# SoftStart_V1_0_TO_PRINT.net
KiCad netlist of a schematic drawn in EAGLE
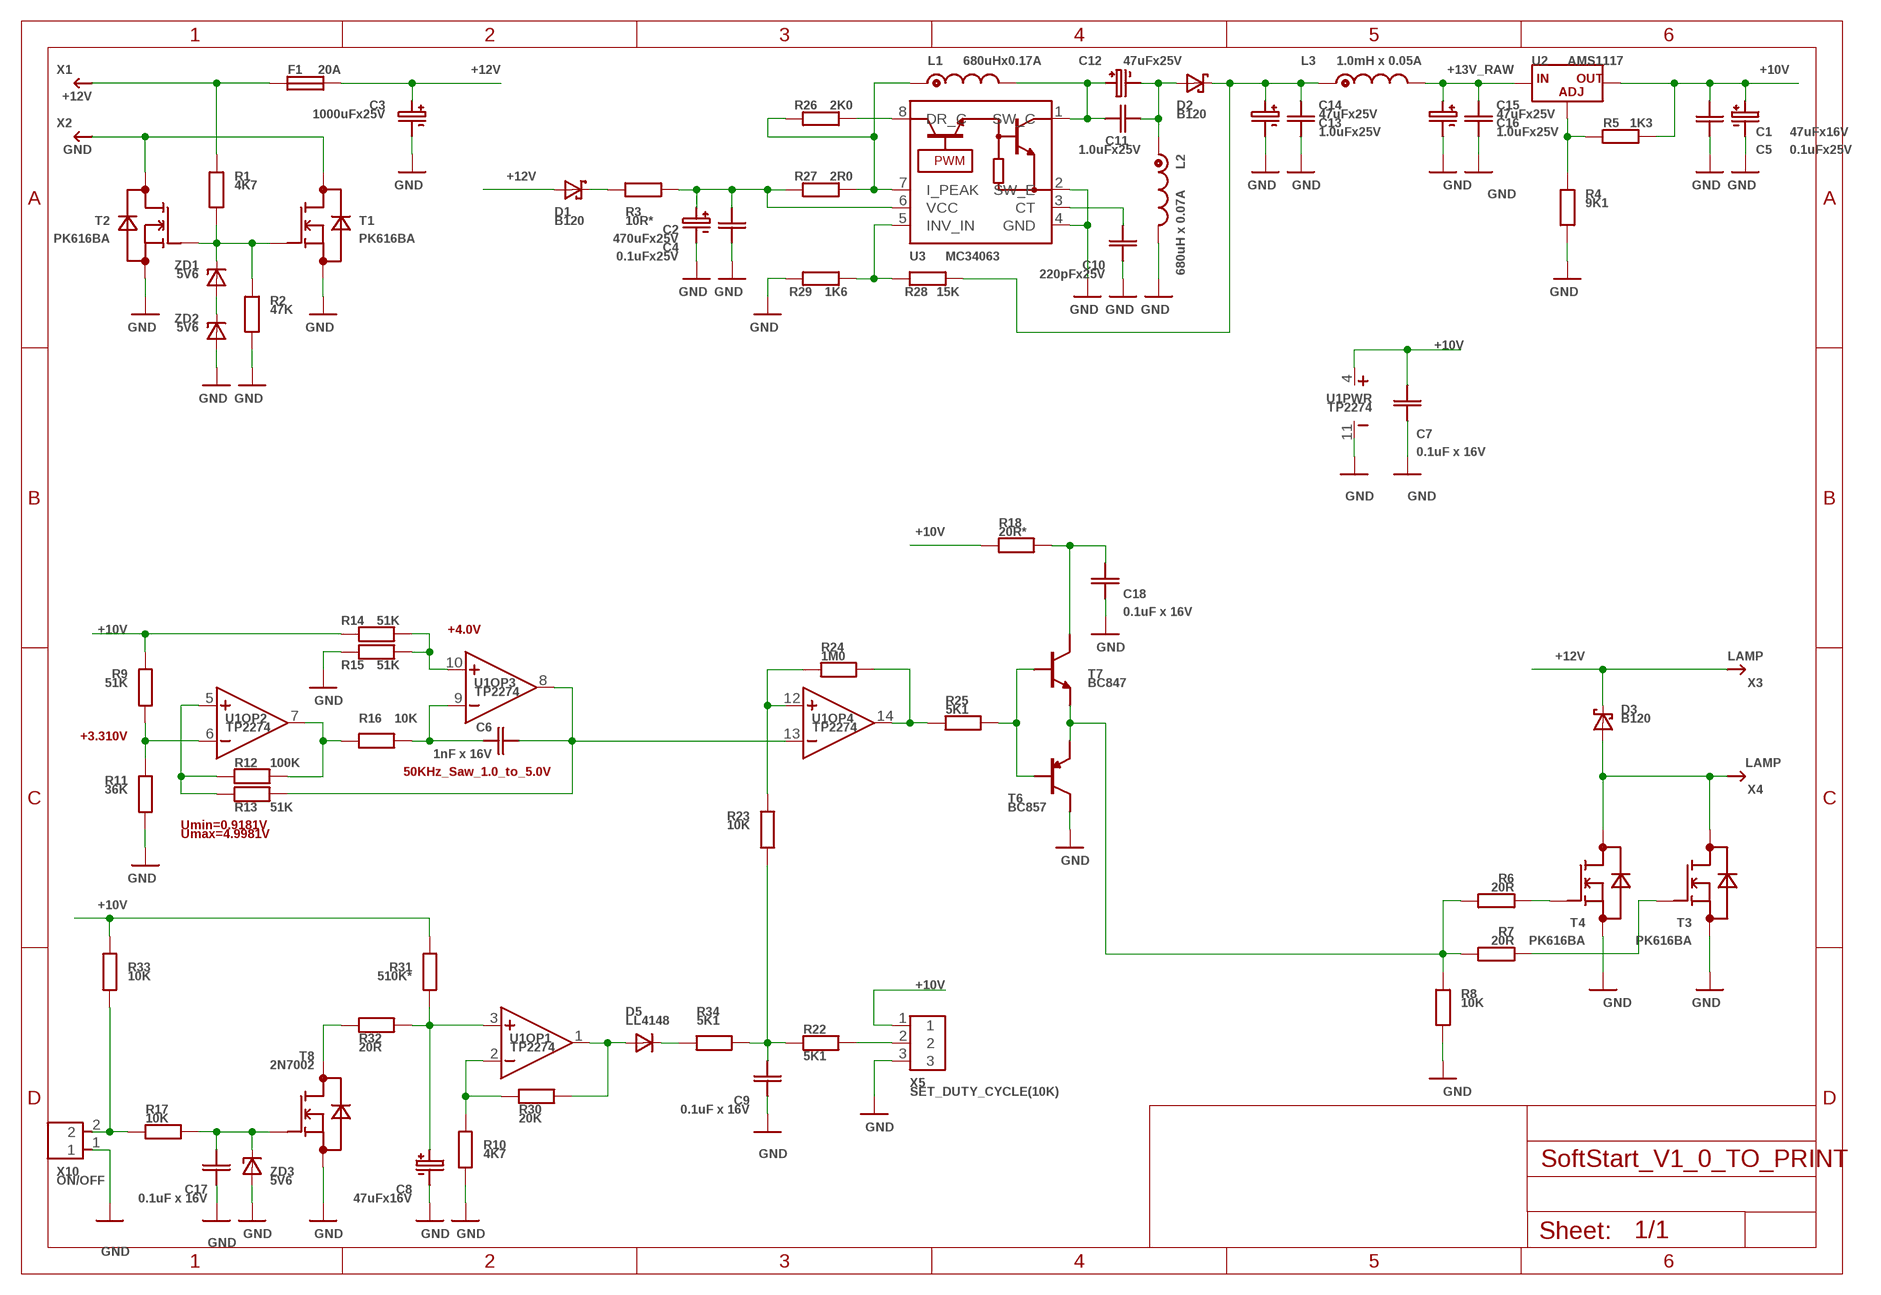
[diagram p0: schematic, sheet 1]

(export (version "E")
  (design (tool "Eeschema 10.0.6"))
  (components
    (comp (ref "C1")
      (value "47uFx16V")
      (footprint "eagle-import:CE_6.3MM")
      (libsource (lib "eagle-import") (part "CE6.3MM"))
    )
    (comp (ref "C2")
      (value "470uFx25V")
      (footprint "eagle-import:CE_10MM")
      (libsource (lib "eagle-import") (part "CE10MM"))
    )
    (comp (ref "C3")
      (value "1000uFx25V")
      (footprint "eagle-import:CE_10MM")
      (libsource (lib "eagle-import") (part "CE10MM"))
    )
    (comp (ref "C4")
      (value "0.1uFx25V")
      (footprint "eagle-import:RSMD_1206")
      (libsource (lib "eagle-import") (part "CSMD_1206"))
    )
    (comp (ref "C5")
      (value "0.1uFx25V")
      (footprint "eagle-import:RSMD_0805")
      (libsource (lib "eagle-import") (part "CSMD_0805"))
    )
    (comp (ref "C6")
      (value "1nF x 16V")
      (footprint "eagle-import:RSMD_0805")
      (libsource (lib "eagle-import") (part "CSMD_0805"))
    )
    (comp (ref "C7")
      (value "0.1uF x 16V")
      (footprint "eagle-import:RSMD_0805")
      (libsource (lib "eagle-import") (part "CSMD_0805"))
    )
    (comp (ref "C8")
      (value "47uFx16V")
      (footprint "eagle-import:CE_6.3MM")
      (libsource (lib "eagle-import") (part "CE6.3MM"))
    )
    (comp (ref "C9")
      (value "0.1uF x 16V")
      (footprint "eagle-import:RSMD_0805")
      (libsource (lib "eagle-import") (part "CSMD_0805"))
    )
    (comp (ref "C10")
      (value "220pFx25V")
      (footprint "eagle-import:RSMD_0805")
      (libsource (lib "eagle-import") (part "CSMD_0805"))
    )
    (comp (ref "C11")
      (value "1.0uFx25V")
      (footprint "eagle-import:RSMD_1206")
      (libsource (lib "eagle-import") (part "CSMD_1206"))
    )
    (comp (ref "C12")
      (value "47uFx25V")
      (footprint "eagle-import:CE_6.3MM")
      (libsource (lib "eagle-import") (part "CE6.3MM"))
    )
    (comp (ref "C13")
      (value "1.0uFx25V")
      (footprint "eagle-import:RSMD_1206")
      (libsource (lib "eagle-import") (part "CSMD_1206"))
    )
    (comp (ref "C14")
      (value "47uFx25V")
      (footprint "eagle-import:CE_6.3MM")
      (libsource (lib "eagle-import") (part "CE6.3MM"))
    )
    (comp (ref "C15")
      (value "47uFx25V")
      (footprint "eagle-import:CE_6.3MM")
      (libsource (lib "eagle-import") (part "CE6.3MM"))
    )
    (comp (ref "C16")
      (value "1.0uFx25V")
      (footprint "eagle-import:RSMD_1206")
      (libsource (lib "eagle-import") (part "CSMD_1206"))
    )
    (comp (ref "C17")
      (value "0.1uF x 16V")
      (footprint "eagle-import:RSMD_0805")
      (libsource (lib "eagle-import") (part "CSMD_0805"))
    )
    (comp (ref "C18")
      (value "0.1uF x 16V")
      (footprint "eagle-import:RSMD_0805")
      (libsource (lib "eagle-import") (part "CSMD_0805"))
    )
    (comp (ref "D1")
      (value "B120")
      (footprint "eagle-import:DO-214AC")
      (libsource (lib "eagle-import") (part "B120(DO-214AC)"))
    )
    (comp (ref "D2")
      (value "B120")
      (footprint "eagle-import:DO-214AC")
      (libsource (lib "eagle-import") (part "B120(DO-214AC)"))
    )
    (comp (ref "D3")
      (value "B120")
      (footprint "eagle-import:DO-214AC")
      (libsource (lib "eagle-import") (part "B120(DO-214AC)"))
    )
    (comp (ref "D5")
      (value "LL4148")
      (footprint "eagle-import:SOD-80")
      (libsource (lib "eagle-import") (part "LL4147SOD-80"))
    )
    (comp (ref "F1")
      (value "20A")
      (footprint "eagle-import:FUSE_AUTO_MINI_ON_TERMINALS")
      (libsource (lib "eagle-import") (part "FUSEAUTO_MINI_TERMINALS"))
    )
    (comp (ref "L1")
      (value "680uHx0.17A")
      (footprint "eagle-import:LCHB0608")
      (libsource (lib "eagle-import") (part "L(LCHB0608)"))
    )
    (comp (ref "L2")
      (value "680uH x 0.07A")
      (footprint "eagle-import:LCHB0608")
      (libsource (lib "eagle-import") (part "L(LCHB0608)"))
    )
    (comp (ref "L3")
      (value "1.0mH x 0.05A")
      (footprint "eagle-import:LCHB0608")
      (libsource (lib "eagle-import") (part "L(LCHB0608)"))
    )
    (comp (ref "R1")
      (value "4K7")
      (footprint "eagle-import:RSMD_0805")
      (libsource (lib "eagle-import") (part "RSMD_0805"))
    )
    (comp (ref "R2")
      (value "47K")
      (footprint "eagle-import:RSMD_0805")
      (libsource (lib "eagle-import") (part "RSMD_0805"))
    )
    (comp (ref "R3")
      (value "10R*")
      (footprint "eagle-import:RSMD_1206_BIG_GAP")
      (libsource (lib "eagle-import") (part "RSMD_1206_BIG_GAP"))
    )
    (comp (ref "R4")
      (value "9K1")
      (footprint "eagle-import:RSMD_0805")
      (libsource (lib "eagle-import") (part "RSMD_0805"))
    )
    (comp (ref "R5")
      (value "1K3")
      (footprint "eagle-import:RSMD_0805")
      (libsource (lib "eagle-import") (part "RSMD_0805"))
    )
    (comp (ref "R6")
      (value "20R")
      (footprint "eagle-import:RSMD_0805")
      (libsource (lib "eagle-import") (part "RSMD_0805"))
    )
    (comp (ref "R7")
      (value "20R")
      (footprint "eagle-import:RSMD_0805")
      (libsource (lib "eagle-import") (part "RSMD_0805"))
    )
    (comp (ref "R8")
      (value "10K")
      (footprint "eagle-import:RSMD_0805")
      (libsource (lib "eagle-import") (part "RSMD_0805"))
    )
    (comp (ref "R9")
      (value "51K")
      (footprint "eagle-import:RSMD_0805")
      (libsource (lib "eagle-import") (part "RSMD_0805"))
    )
    (comp (ref "R10")
      (value "4K7")
      (footprint "eagle-import:RSMD_0805")
      (libsource (lib "eagle-import") (part "RSMD_0805"))
    )
    (comp (ref "R11")
      (value "36K")
      (footprint "eagle-import:RSMD_0805")
      (libsource (lib "eagle-import") (part "RSMD_0805"))
    )
    (comp (ref "R12")
      (value "100K")
      (footprint "eagle-import:RSMD_0805")
      (libsource (lib "eagle-import") (part "RSMD_0805"))
    )
    (comp (ref "R13")
      (value "51K")
      (footprint "eagle-import:RSMD_0805")
      (libsource (lib "eagle-import") (part "RSMD_0805"))
    )
    (comp (ref "R14")
      (value "51K")
      (footprint "eagle-import:RSMD_0805")
      (libsource (lib "eagle-import") (part "RSMD_0805"))
    )
    (comp (ref "R15")
      (value "51K")
      (footprint "eagle-import:RSMD_0805")
      (libsource (lib "eagle-import") (part "RSMD_0805"))
    )
    (comp (ref "R16")
      (value "10K")
      (footprint "eagle-import:RSMD_0805")
      (libsource (lib "eagle-import") (part "RSMD_0805"))
    )
    (comp (ref "R17")
      (value "10K")
      (footprint "eagle-import:RSMD_0805")
      (libsource (lib "eagle-import") (part "RSMD_0805"))
    )
    (comp (ref "R18")
      (value "20R*")
      (footprint "eagle-import:RSMD_1206")
      (libsource (lib "eagle-import") (part "RSMD_1206"))
    )
    (comp (ref "R22")
      (value "5K1")
      (footprint "eagle-import:RSMD_0805")
      (libsource (lib "eagle-import") (part "RSMD_0805"))
    )
    (comp (ref "R23")
      (value "10K")
      (footprint "eagle-import:RSMD_1206_BIG_GAP")
      (libsource (lib "eagle-import") (part "RSMD_1206_BIG_GAP"))
    )
    (comp (ref "R24")
      (value "1M0")
      (footprint "eagle-import:RSMD_0805")
      (libsource (lib "eagle-import") (part "RSMD_0805"))
    )
    (comp (ref "R25")
      (value "5K1")
      (footprint "eagle-import:RSMD_0805")
      (libsource (lib "eagle-import") (part "RSMD_0805"))
    )
    (comp (ref "R26")
      (value "2K0")
      (footprint "eagle-import:RSMD_0805")
      (libsource (lib "eagle-import") (part "RSMD_0805"))
    )
    (comp (ref "R27")
      (value "2R0")
      (footprint "eagle-import:RSMD_1206_BIG_GAP")
      (libsource (lib "eagle-import") (part "RSMD_1206_BIG_GAP"))
    )
    (comp (ref "R28")
      (value "15K")
      (footprint "eagle-import:RSMD_0805")
      (libsource (lib "eagle-import") (part "RSMD_0805"))
    )
    (comp (ref "R29")
      (value "1K6")
      (footprint "eagle-import:RSMD_0805")
      (libsource (lib "eagle-import") (part "RSMD_0805"))
    )
    (comp (ref "R30")
      (value "20K")
      (footprint "eagle-import:RSMD_0805")
      (libsource (lib "eagle-import") (part "RSMD_0805"))
    )
    (comp (ref "R31")
      (value "510K*")
      (footprint "eagle-import:RSMD_0805")
      (libsource (lib "eagle-import") (part "RSMD_0805"))
    )
    (comp (ref "R32")
      (value "20R")
      (footprint "eagle-import:RSMD_0805")
      (libsource (lib "eagle-import") (part "RSMD_0805"))
    )
    (comp (ref "R33")
      (value "10K")
      (footprint "eagle-import:RSMD_0805")
      (libsource (lib "eagle-import") (part "RSMD_0805"))
    )
    (comp (ref "R34")
      (value "5K1")
      (footprint "eagle-import:RSMD_0805")
      (libsource (lib "eagle-import") (part "RSMD_0805"))
    )
    (comp (ref "T1")
      (value "PK616BA")
      (footprint "eagle-import:PDFN_5X6P")
      (libsource (lib "eagle-import") (part "PK616BA(PDFN_5X6P)"))
    )
    (comp (ref "T2")
      (value "PK616BA")
      (footprint "eagle-import:PDFN_5X6P")
      (libsource (lib "eagle-import") (part "PK616BA(PDFN_5X6P)"))
    )
    (comp (ref "T3")
      (value "PK616BA")
      (footprint "eagle-import:PDFN_5X6P")
      (libsource (lib "eagle-import") (part "PK616BA(PDFN_5X6P)"))
    )
    (comp (ref "T4")
      (value "PK616BA")
      (footprint "eagle-import:PDFN_5X6P")
      (libsource (lib "eagle-import") (part "PK616BA(PDFN_5X6P)"))
    )
    (comp (ref "T6")
      (value "BC857")
      (footprint "eagle-import:SOT23")
      (libsource (lib "eagle-import") (part "BC857SOT23"))
    )
    (comp (ref "T7")
      (value "BC847")
      (footprint "eagle-import:SOT23")
      (libsource (lib "eagle-import") (part "BC847SOT23"))
    )
    (comp (ref "T8")
      (value "2N7002")
      (footprint "eagle-import:SOT23")
      (libsource (lib "eagle-import") (part "2N7002SOT23"))
    )
    (comp (ref "U1")
      (value "TP2274")
      (footprint "eagle-import:SOIC14")
      (libsource (lib "eagle-import") (part "LM324"))
    )
    (comp (ref "U2")
      (value "AMS1117")
      (footprint "eagle-import:SOT223(WAVE_SOLDERING)")
      (libsource (lib "eagle-import") (part "AMS1117SOT223_WS"))
    )
    (comp (ref "U3")
      (value "MC34063")
      (footprint "eagle-import:SOIC8")
      (libsource (lib "eagle-import") (part "MC34063(SO-8)"))
    )
    (comp (ref "X1")
      (value "+12V")
      (footprint "eagle-import:RPI_6.3")
      (libsource (lib "eagle-import") (part "RPI_MALE6.3_TWO_HOLES"))
    )
    (comp (ref "X2")
      (value "GND")
      (footprint "eagle-import:RPI_6.3")
      (libsource (lib "eagle-import") (part "RPI_MALE6.3_TWO_HOLES"))
    )
    (comp (ref "X3")
      (value "LAMP")
      (footprint "eagle-import:RPI_6.3")
      (libsource (lib "eagle-import") (part "RPI_MALE6.3_TWO_HOLES"))
    )
    (comp (ref "X4")
      (value "LAMP")
      (footprint "eagle-import:RPI_6.3")
      (libsource (lib "eagle-import") (part "RPI_MALE6.3_TWO_HOLES"))
    )
    (comp (ref "X5")
      (value "SET_DUTY_CYCLE(10K)")
      (footprint "eagle-import:PIN3X1_2.54MM_WITH_CLAMP")
      (libsource (lib "eagle-import") (part "PIN1X3(2.54MM_WITH_CLAMP)"))
    )
    (comp (ref "X10")
      (value "ON/OFF")
      (footprint "eagle-import:PIN2X1_2.54_WITH_CLAMP")
      (libsource (lib "eagle-import") (part "PIN1X22.54MM_WITH_CLAMP"))
    )
    (comp (ref "ZD1")
      (value "5V6")
      (footprint "eagle-import:SOD-80")
      (libsource (lib "eagle-import") (part "ZENNER(SOD_80)"))
    )
    (comp (ref "ZD2")
      (value "5V6")
      (footprint "eagle-import:SOD-80")
      (libsource (lib "eagle-import") (part "ZENNER(SOD_80)"))
    )
    (comp (ref "ZD3")
      (value "5V6")
      (footprint "eagle-import:SOD-80")
      (libsource (lib "eagle-import") (part "ZENNER(SOD_80)"))
    )
  )
  (nets
    (net (code "1") (name "/+10V") (class "Default")
      (node (ref "C1") (pin "PLUS") (pinfunction "PLUS_PLUS") (pintype "bidirectional"))
      (node (ref "C5") (pin "PAD_1") (pinfunction "PIN1_PAD_1") (pintype "bidirectional"))
      (node (ref "C7") (pin "PAD_1") (pinfunction "PIN1_PAD_1") (pintype "bidirectional"))
      (node (ref "R14") (pin "PAD_1") (pinfunction "PIN1_PAD_1") (pintype "passive"))
      (node (ref "R18") (pin "PAD_0") (pinfunction "PIN0_PAD_0") (pintype "passive"))
      (node (ref "R31") (pin "PAD_1") (pinfunction "PIN1_PAD_1") (pintype "passive"))
      (node (ref "R33") (pin "PAD_1") (pinfunction "PIN1_PAD_1") (pintype "passive"))
      (node (ref "R5") (pin "PAD_0") (pinfunction "PIN0_PAD_0") (pintype "passive"))
      (node (ref "R9") (pin "PAD_1") (pinfunction "PIN1_PAD_1") (pintype "passive"))
      (node (ref "U1") (pin "4") (pinfunction "VCC_4") (pintype "power_in"))
      (node (ref "U2") (pin "2") (pinfunction "OUT_2") (pintype "output"))
      (node (ref "U2") (pin "4") (pinfunction "OUT_4") (pintype "output"))
      (node (ref "X5") (pin "1") (pinfunction "1_1") (pintype "passive"))
    )
    (net (code "2") (name "/+12V") (class "Default")
      (node (ref "C3") (pin "PLUS") (pinfunction "PLUS_PLUS") (pintype "bidirectional"))
      (node (ref "D1") (pin "ANODE") (pinfunction "ANODE_ANODE") (pintype "passive"))
      (node (ref "D3") (pin "CATHODE") (pinfunction "CATHODE_CATHODE") (pintype "passive"))
      (node (ref "F1") (pin "PAD0") (pinfunction "PIN0_PAD0") (pintype "passive"))
      (node (ref "X3") (pin "PAD1") (pinfunction "1_PAD1") (pintype "bidirectional"))
      (node (ref "X3") (pin "PAD2") (pinfunction "1_PAD2") (pintype "bidirectional"))
    )
    (net (code "3") (name "/+13V_RAW") (class "Default")
      (node (ref "C15") (pin "PLUS") (pinfunction "PLUS_PLUS") (pintype "bidirectional"))
      (node (ref "C16") (pin "PAD_0") (pinfunction "PIN0_PAD_0") (pintype "bidirectional"))
      (node (ref "L3") (pin "2") (pinfunction "END_2") (pintype "bidirectional"))
      (node (ref "U2") (pin "3") (pinfunction "IN_3") (pintype "input"))
    )
    (net (code "4") (name "GND") (class "Default")
      (node (ref "C1") (pin "MINUS") (pinfunction "MINUS_MINUS") (pintype "bidirectional"))
      (node (ref "C10") (pin "PAD_0") (pinfunction "PIN0_PAD_0") (pintype "bidirectional"))
      (node (ref "C13") (pin "PAD_1") (pinfunction "PIN1_PAD_1") (pintype "bidirectional"))
      (node (ref "C14") (pin "MINUS") (pinfunction "MINUS_MINUS") (pintype "bidirectional"))
      (node (ref "C15") (pin "MINUS") (pinfunction "MINUS_MINUS") (pintype "bidirectional"))
      (node (ref "C16") (pin "PAD_1") (pinfunction "PIN1_PAD_1") (pintype "bidirectional"))
      (node (ref "C17") (pin "PAD_0") (pinfunction "PIN0_PAD_0") (pintype "bidirectional"))
      (node (ref "C18") (pin "PAD_0") (pinfunction "PIN0_PAD_0") (pintype "bidirectional"))
      (node (ref "C2") (pin "MINUS") (pinfunction "MINUS_MINUS") (pintype "bidirectional"))
      (node (ref "C3") (pin "MINUS") (pinfunction "MINUS_MINUS") (pintype "bidirectional"))
      (node (ref "C4") (pin "PAD_0") (pinfunction "PIN0_PAD_0") (pintype "bidirectional"))
      (node (ref "C5") (pin "PAD_0") (pinfunction "PIN0_PAD_0") (pintype "bidirectional"))
      (node (ref "C7") (pin "PAD_0") (pinfunction "PIN0_PAD_0") (pintype "bidirectional"))
      (node (ref "C8") (pin "MINUS") (pinfunction "MINUS_MINUS") (pintype "bidirectional"))
      (node (ref "C9") (pin "PAD_0") (pinfunction "PIN0_PAD_0") (pintype "bidirectional"))
      (node (ref "L2") (pin "2") (pinfunction "END_2") (pintype "bidirectional"))
      (node (ref "R10") (pin "PAD_0") (pinfunction "PIN0_PAD_0") (pintype "passive"))
      (node (ref "R11") (pin "PAD_0") (pinfunction "PIN0_PAD_0") (pintype "passive"))
      (node (ref "R15") (pin "PAD_1") (pinfunction "PIN1_PAD_1") (pintype "passive"))
      (node (ref "R2") (pin "PAD_0") (pinfunction "PIN0_PAD_0") (pintype "passive"))
      (node (ref "R29") (pin "PAD_0") (pinfunction "PIN0_PAD_0") (pintype "passive"))
      (node (ref "R4") (pin "PAD_0") (pinfunction "PIN0_PAD_0") (pintype "passive"))
      (node (ref "R8") (pin "PAD_1") (pinfunction "PIN1_PAD_1") (pintype "passive"))
      (node (ref "T1") (pin "S1") (pinfunction "SOURCE_S1") (pintype "bidirectional"))
      (node (ref "T1") (pin "S2") (pinfunction "SOURCE_S2") (pintype "bidirectional"))
      (node (ref "T1") (pin "S3") (pinfunction "SOURCE_S3") (pintype "bidirectional"))
      (node (ref "T2") (pin "S1") (pinfunction "SOURCE_S1") (pintype "bidirectional"))
      (node (ref "T2") (pin "S2") (pinfunction "SOURCE_S2") (pintype "bidirectional"))
      (node (ref "T2") (pin "S3") (pinfunction "SOURCE_S3") (pintype "bidirectional"))
      (node (ref "T3") (pin "S1") (pinfunction "SOURCE_S1") (pintype "bidirectional"))
      (node (ref "T3") (pin "S2") (pinfunction "SOURCE_S2") (pintype "bidirectional"))
      (node (ref "T3") (pin "S3") (pinfunction "SOURCE_S3") (pintype "bidirectional"))
      (node (ref "T4") (pin "S1") (pinfunction "SOURCE_S1") (pintype "bidirectional"))
      (node (ref "T4") (pin "S2") (pinfunction "SOURCE_S2") (pintype "bidirectional"))
      (node (ref "T4") (pin "S3") (pinfunction "SOURCE_S3") (pintype "bidirectional"))
      (node (ref "T6") (pin "3") (pinfunction "C_3") (pintype "bidirectional"))
      (node (ref "T8") (pin "2") (pinfunction "SOURCE_2") (pintype "bidirectional"))
      (node (ref "U1") (pin "11") (pinfunction "GND_11") (pintype "power_in"))
      (node (ref "U3") (pin "2") (pinfunction "SW_E_2") (pintype "bidirectional"))
      (node (ref "U3") (pin "4") (pinfunction "GND_4") (pintype "bidirectional"))
      (node (ref "X10") (pin "1") (pinfunction "1_1") (pintype "bidirectional"))
      (node (ref "X5") (pin "3") (pinfunction "3_3") (pintype "passive"))
      (node (ref "ZD2") (pin "ANODE") (pinfunction "ANODE_ANODE") (pintype "passive"))
      (node (ref "ZD3") (pin "ANODE") (pinfunction "ANODE_ANODE") (pintype "passive"))
    )
    (net (code "5") (name "Net-(C4-PIN1)") (class "Default")
      (node (ref "C2") (pin "PLUS") (pinfunction "PLUS_PLUS") (pintype "bidirectional"))
      (node (ref "C4") (pin "PAD_1") (pinfunction "PIN1_PAD_1") (pintype "bidirectional"))
      (node (ref "R27") (pin "PAD_1") (pinfunction "PIN1_PAD_1") (pintype "passive"))
      (node (ref "R3") (pin "PAD_0") (pinfunction "PIN0_PAD_0") (pintype "passive"))
      (node (ref "U3") (pin "6") (pinfunction "VCC_6") (pintype "bidirectional"))
    )
    (net (code "6") (name "Net-(C6-PIN0)") (class "Default")
      (node (ref "C6") (pin "PAD_0") (pinfunction "PIN0_PAD_0") (pintype "bidirectional"))
      (node (ref "R13") (pin "PAD_1") (pinfunction "PIN1_PAD_1") (pintype "passive"))
      (node (ref "U1") (pin "13") (pinfunction "IN-_13") (pintype "input"))
      (node (ref "U1") (pin "8") (pinfunction "OUT_8") (pintype "output"))
    )
    (net (code "7") (name "Net-(C6-PIN1)") (class "Default")
      (node (ref "C6") (pin "PAD_1") (pinfunction "PIN1_PAD_1") (pintype "bidirectional"))
      (node (ref "R16") (pin "PAD_1") (pinfunction "PIN1_PAD_1") (pintype "passive"))
      (node (ref "U1") (pin "9") (pinfunction "IN-_9") (pintype "input"))
    )
    (net (code "8") (name "Net-(C9-PIN1)") (class "Default")
      (node (ref "C9") (pin "PAD_1") (pinfunction "PIN1_PAD_1") (pintype "bidirectional"))
      (node (ref "R22") (pin "PAD_1") (pinfunction "PIN1_PAD_1") (pintype "passive"))
      (node (ref "R23") (pin "PAD_0") (pinfunction "PIN0_PAD_0") (pintype "passive"))
      (node (ref "R34") (pin "PAD_1") (pinfunction "PIN1_PAD_1") (pintype "passive"))
    )
    (net (code "9") (name "Net-(C10-PIN1)") (class "Default")
      (node (ref "C10") (pin "PAD_1") (pinfunction "PIN1_PAD_1") (pintype "bidirectional"))
      (node (ref "U3") (pin "3") (pinfunction "CT_3") (pintype "bidirectional"))
    )
    (net (code "10") (name "Net-(C11-PIN0)") (class "Default")
      (node (ref "C11") (pin "PAD_0") (pinfunction "PIN0_PAD_0") (pintype "bidirectional"))
      (node (ref "C12") (pin "MINUS") (pinfunction "MINUS_MINUS") (pintype "bidirectional"))
      (node (ref "D2") (pin "ANODE") (pinfunction "ANODE_ANODE") (pintype "passive"))
      (node (ref "L2") (pin "1") (pinfunction "START_1") (pintype "bidirectional"))
    )
    (net (code "11") (name "Net-(C11-PIN1)") (class "Default")
      (node (ref "C11") (pin "PAD_1") (pinfunction "PIN1_PAD_1") (pintype "bidirectional"))
      (node (ref "C12") (pin "PLUS") (pinfunction "PLUS_PLUS") (pintype "bidirectional"))
      (node (ref "L1") (pin "2") (pinfunction "END_2") (pintype "bidirectional"))
      (node (ref "U3") (pin "1") (pinfunction "SW_C_1") (pintype "bidirectional"))
    )
    (net (code "12") (name "Net-(C13-PIN0)") (class "Default")
      (node (ref "C13") (pin "PAD_0") (pinfunction "PIN0_PAD_0") (pintype "bidirectional"))
      (node (ref "C14") (pin "PLUS") (pinfunction "PLUS_PLUS") (pintype "bidirectional"))
      (node (ref "D2") (pin "CATHODE") (pinfunction "CATHODE_CATHODE") (pintype "passive"))
      (node (ref "L3") (pin "1") (pinfunction "START_1") (pintype "bidirectional"))
      (node (ref "R28") (pin "PAD_1") (pinfunction "PIN1_PAD_1") (pintype "passive"))
    )
    (net (code "13") (name "Net-(C17-PIN1)") (class "Default")
      (node (ref "C17") (pin "PAD_1") (pinfunction "PIN1_PAD_1") (pintype "bidirectional"))
      (node (ref "R17") (pin "PAD_0") (pinfunction "PIN0_PAD_0") (pintype "passive"))
      (node (ref "T8") (pin "1") (pinfunction "GATE_1") (pintype "bidirectional"))
      (node (ref "ZD3") (pin "CATHODE") (pinfunction "CATHODE_CATHODE") (pintype "passive"))
    )
    (net (code "14") (name "Net-(C18-PIN1)") (class "Default")
      (node (ref "C18") (pin "PAD_1") (pinfunction "PIN1_PAD_1") (pintype "bidirectional"))
      (node (ref "R18") (pin "PAD_1") (pinfunction "PIN1_PAD_1") (pintype "passive"))
      (node (ref "T7") (pin "3") (pinfunction "C_3") (pintype "bidirectional"))
    )
    (net (code "15") (name "Net-(D3-PadANODE)") (class "Default")
      (node (ref "D3") (pin "ANODE") (pinfunction "ANODE_ANODE") (pintype "passive"))
      (node (ref "T3") (pin "D") (pinfunction "DRAIN_D") (pintype "bidirectional"))
      (node (ref "T3") (pin "D1") (pinfunction "DRAIN_D1") (pintype "bidirectional"))
      (node (ref "T3") (pin "D2") (pinfunction "DRAIN_D2") (pintype "bidirectional"))
      (node (ref "T3") (pin "D3") (pinfunction "DRAIN_D3") (pintype "bidirectional"))
      (node (ref "T3") (pin "D4") (pinfunction "DRAIN_D4") (pintype "bidirectional"))
      (node (ref "T4") (pin "D") (pinfunction "DRAIN_D") (pintype "bidirectional"))
      (node (ref "T4") (pin "D1") (pinfunction "DRAIN_D1") (pintype "bidirectional"))
      (node (ref "T4") (pin "D2") (pinfunction "DRAIN_D2") (pintype "bidirectional"))
      (node (ref "T4") (pin "D3") (pinfunction "DRAIN_D3") (pintype "bidirectional"))
      (node (ref "T4") (pin "D4") (pinfunction "DRAIN_D4") (pintype "bidirectional"))
      (node (ref "X4") (pin "PAD1") (pinfunction "1_PAD1") (pintype "bidirectional"))
      (node (ref "X4") (pin "PAD2") (pinfunction "1_PAD2") (pintype "bidirectional"))
    )
    (net (code "16") (name "Net-(F1-PIN1)") (class "Default")
      (node (ref "F1") (pin "PAD1") (pinfunction "PIN1_PAD1") (pintype "passive"))
      (node (ref "R1") (pin "PAD_1") (pinfunction "PIN1_PAD_1") (pintype "passive"))
      (node (ref "X1") (pin "PAD1") (pinfunction "1_PAD1") (pintype "bidirectional"))
      (node (ref "X1") (pin "PAD2") (pinfunction "1_PAD2") (pintype "bidirectional"))
    )
    (net (code "17") (name "Net-(L1-START)") (class "Default")
      (node (ref "L1") (pin "1") (pinfunction "START_1") (pintype "bidirectional"))
      (node (ref "R26") (pin "PAD_1") (pinfunction "PIN1_PAD_1") (pintype "passive"))
      (node (ref "R27") (pin "PAD_0") (pinfunction "PIN0_PAD_0") (pintype "passive"))
      (node (ref "U3") (pin "7") (pinfunction "I_PEAK_7") (pintype "bidirectional"))
    )
    (net (code "18") (name "Net-(R1-PIN0)") (class "Default")
      (node (ref "R1") (pin "PAD_0") (pinfunction "PIN0_PAD_0") (pintype "passive"))
      (node (ref "R2") (pin "PAD_1") (pinfunction "PIN1_PAD_1") (pintype "passive"))
      (node (ref "T1") (pin "G") (pinfunction "GATE_G") (pintype "bidirectional"))
      (node (ref "T2") (pin "G") (pinfunction "GATE_G") (pintype "bidirectional"))
      (node (ref "ZD1") (pin "CATHODE") (pinfunction "CATHODE_CATHODE") (pintype "passive"))
    )
    (net (code "19") (name "Net-(R3-PIN1)") (class "Default")
      (node (ref "D1") (pin "CATHODE") (pinfunction "CATHODE_CATHODE") (pintype "passive"))
      (node (ref "R3") (pin "PAD_1") (pinfunction "PIN1_PAD_1") (pintype "passive"))
    )
    (net (code "20") (name "Net-(R4-PIN1)") (class "Default")
      (node (ref "R4") (pin "PAD_1") (pinfunction "PIN1_PAD_1") (pintype "passive"))
      (node (ref "R5") (pin "PAD_1") (pinfunction "PIN1_PAD_1") (pintype "passive"))
      (node (ref "U2") (pin "1") (pinfunction "ADJ_1") (pintype "input"))
    )
    (net (code "21") (name "Net-(R6-PIN0)") (class "Default")
      (node (ref "R6") (pin "PAD_0") (pinfunction "PIN0_PAD_0") (pintype "passive"))
      (node (ref "T4") (pin "G") (pinfunction "GATE_G") (pintype "bidirectional"))
    )
    (net (code "22") (name "Net-(R6-PIN1)") (class "Default")
      (node (ref "R6") (pin "PAD_1") (pinfunction "PIN1_PAD_1") (pintype "passive"))
      (node (ref "R7") (pin "PAD_1") (pinfunction "PIN1_PAD_1") (pintype "passive"))
      (node (ref "R8") (pin "PAD_0") (pinfunction "PIN0_PAD_0") (pintype "passive"))
      (node (ref "T6") (pin "2") (pinfunction "E_2") (pintype "bidirectional"))
      (node (ref "T7") (pin "2") (pinfunction "E_2") (pintype "bidirectional"))
    )
    (net (code "23") (name "Net-(R7-PIN0)") (class "Default")
      (node (ref "R7") (pin "PAD_0") (pinfunction "PIN0_PAD_0") (pintype "passive"))
      (node (ref "T3") (pin "G") (pinfunction "GATE_G") (pintype "bidirectional"))
    )
    (net (code "24") (name "Net-(R10-PIN1)") (class "Default")
      (node (ref "R10") (pin "PAD_1") (pinfunction "PIN1_PAD_1") (pintype "passive"))
      (node (ref "R30") (pin "PAD_1") (pinfunction "PIN1_PAD_1") (pintype "passive"))
      (node (ref "U1") (pin "2") (pinfunction "IN-_2") (pintype "input"))
    )
    (net (code "25") (name "Net-(R11-PIN1)") (class "Default")
      (node (ref "R11") (pin "PAD_1") (pinfunction "PIN1_PAD_1") (pintype "passive"))
      (node (ref "R9") (pin "PAD_0") (pinfunction "PIN0_PAD_0") (pintype "passive"))
      (node (ref "U1") (pin "6") (pinfunction "IN-_6") (pintype "input"))
    )
    (net (code "26") (name "Net-(R12-PIN0)") (class "Default")
      (node (ref "R12") (pin "PAD_0") (pinfunction "PIN0_PAD_0") (pintype "passive"))
      (node (ref "R13") (pin "PAD_0") (pinfunction "PIN0_PAD_0") (pintype "passive"))
      (node (ref "U1") (pin "5") (pinfunction "IN+_5") (pintype "input"))
    )
    (net (code "27") (name "Net-(R12-PIN1)") (class "Default")
      (node (ref "R12") (pin "PAD_1") (pinfunction "PIN1_PAD_1") (pintype "passive"))
      (node (ref "R16") (pin "PAD_0") (pinfunction "PIN0_PAD_0") (pintype "passive"))
      (node (ref "U1") (pin "7") (pinfunction "OUT_7") (pintype "output"))
    )
    (net (code "28") (name "Net-(R14-PIN0)") (class "Default")
      (node (ref "R14") (pin "PAD_0") (pinfunction "PIN0_PAD_0") (pintype "passive"))
      (node (ref "R15") (pin "PAD_0") (pinfunction "PIN0_PAD_0") (pintype "passive"))
      (node (ref "U1") (pin "10") (pinfunction "IN+_10") (pintype "input"))
    )
    (net (code "29") (name "Net-(R17-PIN1)") (class "Default")
      (node (ref "R17") (pin "PAD_1") (pinfunction "PIN1_PAD_1") (pintype "passive"))
      (node (ref "R33") (pin "PAD_0") (pinfunction "PIN0_PAD_0") (pintype "passive"))
      (node (ref "X10") (pin "2") (pinfunction "2_2") (pintype "bidirectional"))
    )
    (net (code "30") (name "Net-(R22-PIN0)") (class "Default")
      (node (ref "R22") (pin "PAD_0") (pinfunction "PIN0_PAD_0") (pintype "passive"))
      (node (ref "X5") (pin "2") (pinfunction "2_2") (pintype "passive"))
    )
    (net (code "31") (name "Net-(R23-PIN1)") (class "Default")
      (node (ref "R23") (pin "PAD_1") (pinfunction "PIN1_PAD_1") (pintype "passive"))
      (node (ref "R24") (pin "PAD_0") (pinfunction "PIN0_PAD_0") (pintype "passive"))
      (node (ref "U1") (pin "12") (pinfunction "IN+_12") (pintype "input"))
    )
    (net (code "32") (name "Net-(R24-PIN1)") (class "Default")
      (node (ref "R24") (pin "PAD_1") (pinfunction "PIN1_PAD_1") (pintype "passive"))
      (node (ref "R25") (pin "PAD_0") (pinfunction "PIN0_PAD_0") (pintype "passive"))
      (node (ref "U1") (pin "14") (pinfunction "OUT_14") (pintype "output"))
    )
    (net (code "33") (name "Net-(R25-PIN1)") (class "Default")
      (node (ref "R25") (pin "PAD_1") (pinfunction "PIN1_PAD_1") (pintype "passive"))
      (node (ref "T6") (pin "1") (pinfunction "B_1") (pintype "bidirectional"))
      (node (ref "T7") (pin "1") (pinfunction "B_1") (pintype "bidirectional"))
    )
    (net (code "34") (name "Net-(R26-PIN0)") (class "Default")
      (node (ref "R26") (pin "PAD_0") (pinfunction "PIN0_PAD_0") (pintype "passive"))
      (node (ref "U3") (pin "8") (pinfunction "DR_C_8") (pintype "bidirectional"))
    )
    (net (code "35") (name "Net-(R28-PIN0)") (class "Default")
      (node (ref "R28") (pin "PAD_0") (pinfunction "PIN0_PAD_0") (pintype "passive"))
      (node (ref "R29") (pin "PAD_1") (pinfunction "PIN1_PAD_1") (pintype "passive"))
      (node (ref "U3") (pin "5") (pinfunction "INV_IN_5") (pintype "bidirectional"))
    )
    (net (code "36") (name "Net-(R30-PIN0)") (class "Default")
      (node (ref "D5") (pin "ANODE") (pinfunction "ANODE_ANODE") (pintype "passive"))
      (node (ref "R30") (pin "PAD_0") (pinfunction "PIN0_PAD_0") (pintype "passive"))
      (node (ref "U1") (pin "1") (pinfunction "OUT_1") (pintype "output"))
    )
    (net (code "37") (name "Net-(R31-PIN0)") (class "Default")
      (node (ref "C8") (pin "PLUS") (pinfunction "PLUS_PLUS") (pintype "bidirectional"))
      (node (ref "R31") (pin "PAD_0") (pinfunction "PIN0_PAD_0") (pintype "passive"))
      (node (ref "R32") (pin "PAD_1") (pinfunction "PIN1_PAD_1") (pintype "passive"))
      (node (ref "U1") (pin "3") (pinfunction "IN+_3") (pintype "input"))
    )
    (net (code "38") (name "Net-(R32-PIN0)") (class "Default")
      (node (ref "R32") (pin "PAD_0") (pinfunction "PIN0_PAD_0") (pintype "passive"))
      (node (ref "T8") (pin "3") (pinfunction "DRAIN_3") (pintype "bidirectional"))
    )
    (net (code "39") (name "Net-(R34-PIN0)") (class "Default")
      (node (ref "D5") (pin "CATHODE") (pinfunction "CATHODE_CATHODE") (pintype "passive"))
      (node (ref "R34") (pin "PAD_0") (pinfunction "PIN0_PAD_0") (pintype "passive"))
    )
    (net (code "40") (name "Net-(T1-DRAIN-PadD)") (class "Default")
      (node (ref "T1") (pin "D") (pinfunction "DRAIN_D") (pintype "bidirectional"))
      (node (ref "T1") (pin "D1") (pinfunction "DRAIN_D1") (pintype "bidirectional"))
      (node (ref "T1") (pin "D2") (pinfunction "DRAIN_D2") (pintype "bidirectional"))
      (node (ref "T1") (pin "D3") (pinfunction "DRAIN_D3") (pintype "bidirectional"))
      (node (ref "T1") (pin "D4") (pinfunction "DRAIN_D4") (pintype "bidirectional"))
      (node (ref "T2") (pin "D") (pinfunction "DRAIN_D") (pintype "bidirectional"))
      (node (ref "T2") (pin "D1") (pinfunction "DRAIN_D1") (pintype "bidirectional"))
      (node (ref "T2") (pin "D2") (pinfunction "DRAIN_D2") (pintype "bidirectional"))
      (node (ref "T2") (pin "D3") (pinfunction "DRAIN_D3") (pintype "bidirectional"))
      (node (ref "T2") (pin "D4") (pinfunction "DRAIN_D4") (pintype "bidirectional"))
      (node (ref "X2") (pin "PAD1") (pinfunction "1_PAD1") (pintype "bidirectional"))
      (node (ref "X2") (pin "PAD2") (pinfunction "1_PAD2") (pintype "bidirectional"))
    )
    (net (code "41") (name "Net-(ZD1-PadANODE)") (class "Default")
      (node (ref "ZD1") (pin "ANODE") (pinfunction "ANODE_ANODE") (pintype "passive"))
      (node (ref "ZD2") (pin "CATHODE") (pinfunction "CATHODE_CATHODE") (pintype "passive"))
    )
  )
)
